# akabeacon_square_type2_MDBT40.net
KiCad netlist of a schematic drawn in EAGLE
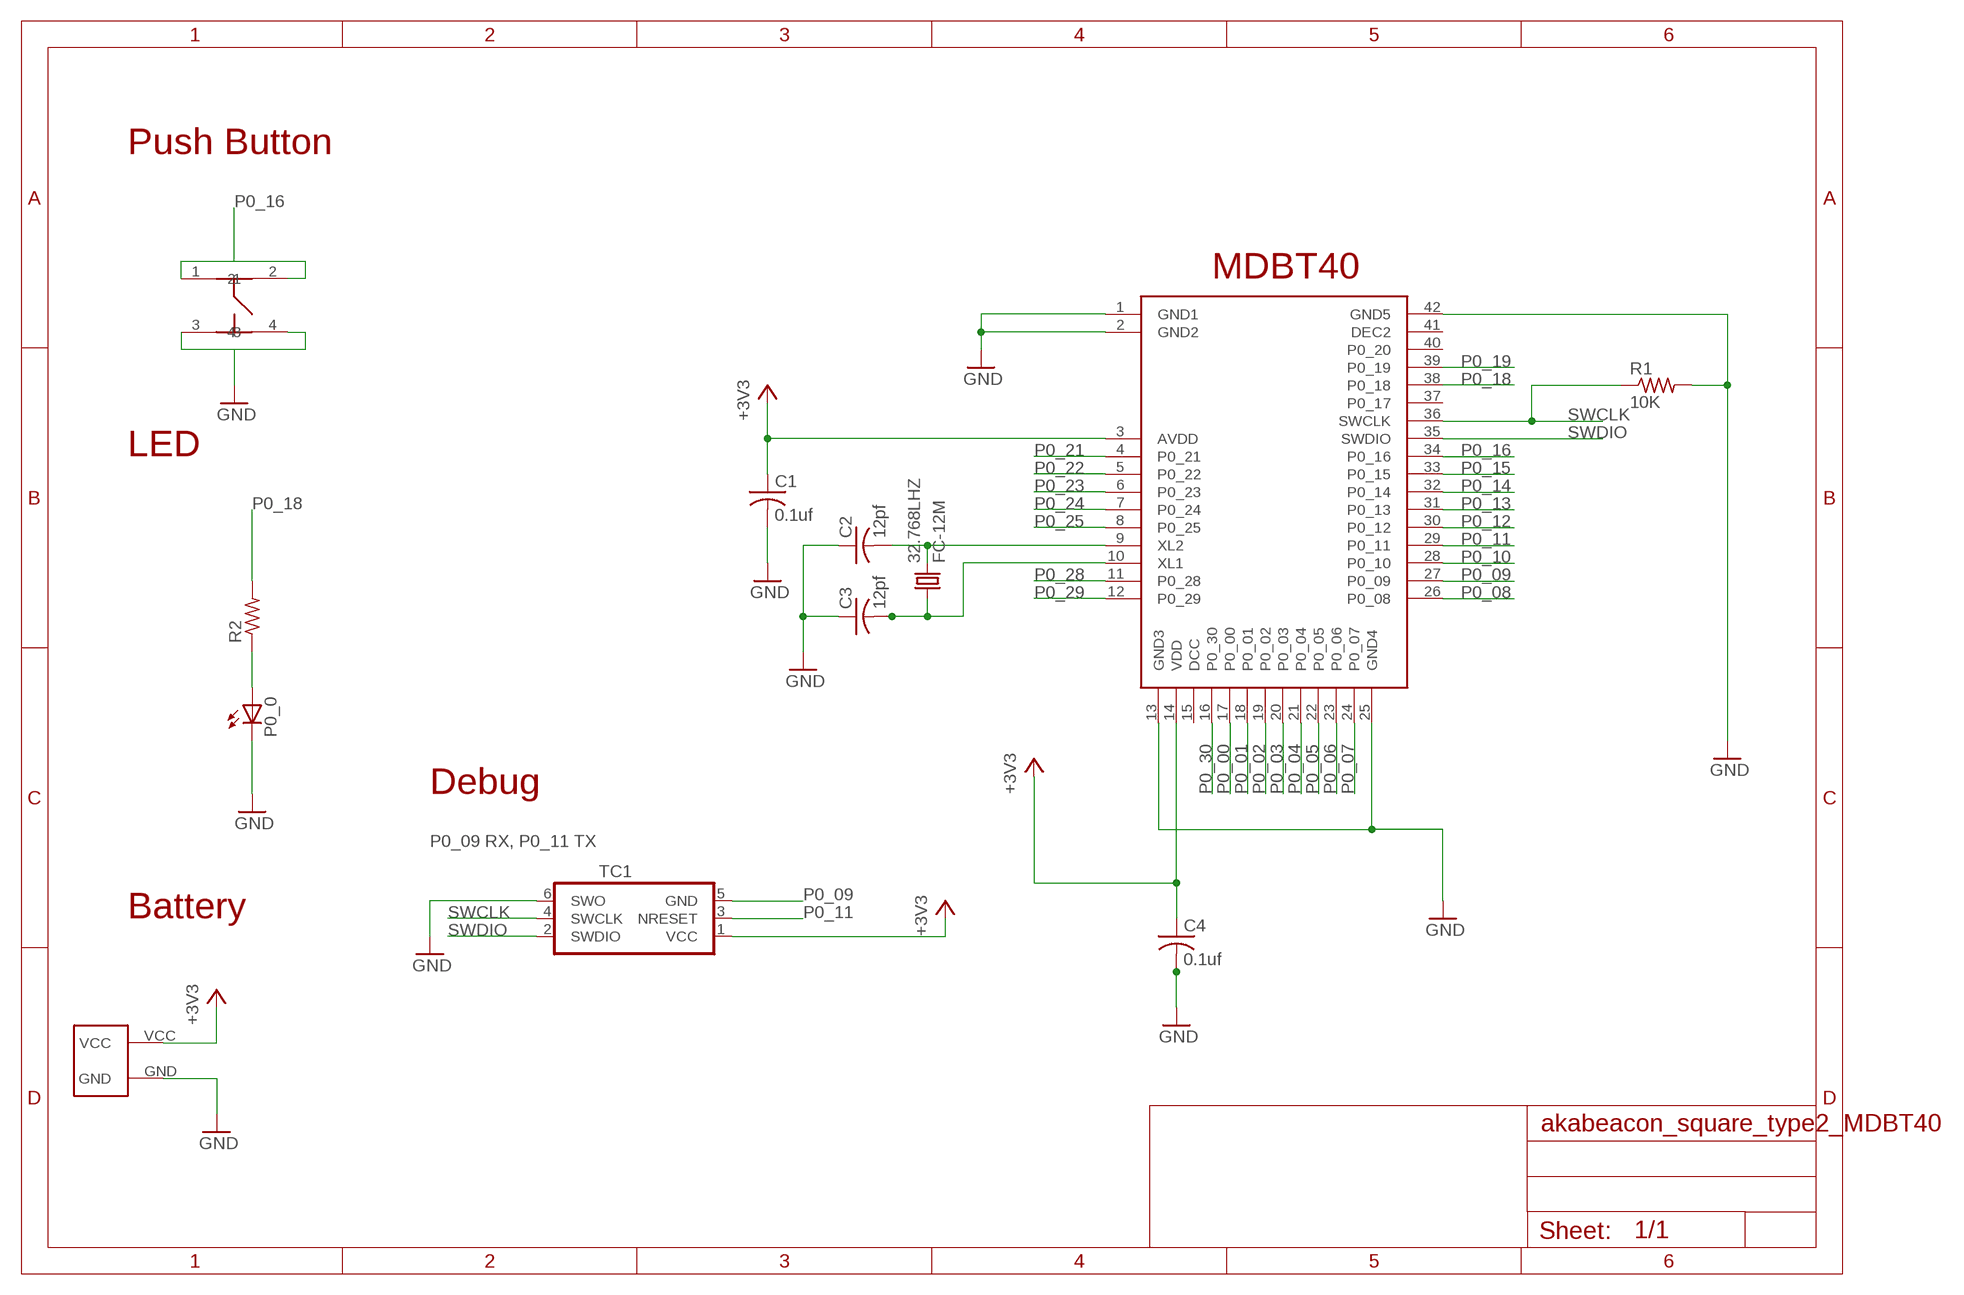
[diagram p0: schematic, sheet 1]

(export (version "E")
  (design (tool "Eeschema 10.0.6"))
  (components
    (comp (ref "32.768LHZ")
      (value "FC-12M")
      (footprint "eagle-import:FC-12M")
      (libsource (lib "eagle-import") (part "FC-12M"))
    )
    (comp (ref "C1")
      (value "0.1uf")
      (footprint "eagle-import:C0603")
      (libsource (lib "eagle-import") (part "C-USC0603"))
    )
    (comp (ref "C2")
      (value "12pf")
      (footprint "eagle-import:C0603")
      (libsource (lib "eagle-import") (part "C-USC0603"))
    )
    (comp (ref "C3")
      (value "12pf")
      (footprint "eagle-import:C0603")
      (libsource (lib "eagle-import") (part "C-USC0603"))
    )
    (comp (ref "C4")
      (value "0.1uf")
      (footprint "eagle-import:C0603")
      (libsource (lib "eagle-import") (part "C-USC0603"))
    )
    (comp (ref "P0_0")
      (value "LEDCHIP-LED0603")
      (footprint "eagle-import:CHIP-LED0603")
      (libsource (lib "eagle-import") (part "LEDCHIP-LED0603"))
    )
    (comp (ref "R1")
      (value "10K")
      (footprint "eagle-import:R0603")
      (libsource (lib "eagle-import") (part "R-US_R0603"))
    )
    (comp (ref "R2")
      (value "R-US_R0603")
      (footprint "eagle-import:R0603")
      (libsource (lib "eagle-import") (part "R-US_R0603"))
    )
    (comp (ref "TC1")
      (value "TC2030-IDC-NL")
      (footprint "eagle-import:TC2030-IDC-NL")
      (libsource (lib "eagle-import") (part "TC2030-IDC-NL"))
    )
    (comp (ref "U$3")
      (value "RAYTAC-MDBT40")
      (footprint "eagle-import:RAYTAC-MDBT40")
      (libsource (lib "eagle-import") (part "RAYTAC-MDBT40"))
    )
    (comp (ref "U$5")
      (value "SQUARE-TYPE2-TC2030")
      (footprint "eagle-import:SQUARE-TYPE2-TC2030")
      (libsource (lib "eagle-import") (part "SQUARE-TYPE2-TC2030"))
    )
    (comp (ref "U$6")
      (value "SWICTH-4P(KMR2)")
      (footprint "eagle-import:SWITCH-4P(KMR2)")
      (libsource (lib "eagle-import") (part "SWICTH-4P(KMR2)"))
    )
  )
  (nets
    (net (code "1") (name "+3V3") (class "Default")
      (node (ref "C1") (pin "1") (pinfunction "1_1") (pintype "passive"))
      (node (ref "C4") (pin "1") (pinfunction "1_1") (pintype "passive"))
      (node (ref "TC1") (pin "1") (pinfunction "VCC_1") (pintype "passive"))
      (node (ref "U$3") (pin "14") (pinfunction "VDD_14") (pintype "bidirectional"))
      (node (ref "U$3") (pin "3") (pinfunction "AVDD_3") (pintype "bidirectional"))
      (node (ref "U$5") (pin "VCC") (pinfunction "VCC_VCC") (pintype "bidirectional"))
    )
    (net (code "2") (name "/P0_00") (class "Default")
      (node (ref "U$3") (pin "17") (pinfunction "P0_00_17") (pintype "bidirectional"))
    )
    (net (code "3") (name "/P0_01") (class "Default")
      (node (ref "U$3") (pin "18") (pinfunction "P0_01_18") (pintype "bidirectional"))
    )
    (net (code "4") (name "/P0_02") (class "Default")
      (node (ref "U$3") (pin "19") (pinfunction "P0_02_19") (pintype "bidirectional"))
    )
    (net (code "5") (name "/P0_03") (class "Default")
      (node (ref "U$3") (pin "20") (pinfunction "P0_03_20") (pintype "bidirectional"))
    )
    (net (code "6") (name "/P0_04") (class "Default")
      (node (ref "U$3") (pin "21") (pinfunction "P0_04_21") (pintype "bidirectional"))
    )
    (net (code "7") (name "/P0_05") (class "Default")
      (node (ref "U$3") (pin "22") (pinfunction "P0_05_22") (pintype "bidirectional"))
    )
    (net (code "8") (name "/P0_06") (class "Default")
      (node (ref "U$3") (pin "23") (pinfunction "P0_06_23") (pintype "bidirectional"))
    )
    (net (code "9") (name "/P0_07") (class "Default")
      (node (ref "U$3") (pin "24") (pinfunction "P0_07_24") (pintype "bidirectional"))
    )
    (net (code "10") (name "/P0_08") (class "Default")
      (node (ref "U$3") (pin "26") (pinfunction "P0_08_26") (pintype "bidirectional"))
    )
    (net (code "11") (name "/P0_09") (class "Default")
      (node (ref "TC1") (pin "5") (pinfunction "GND_5") (pintype "passive"))
      (node (ref "U$3") (pin "27") (pinfunction "P0_09_27") (pintype "bidirectional"))
    )
    (net (code "12") (name "/P0_10") (class "Default")
      (node (ref "U$3") (pin "28") (pinfunction "P0_10_28") (pintype "bidirectional"))
    )
    (net (code "13") (name "/P0_11") (class "Default")
      (node (ref "TC1") (pin "3") (pinfunction "NRESET_3") (pintype "passive"))
      (node (ref "U$3") (pin "29") (pinfunction "P0_11_29") (pintype "bidirectional"))
    )
    (net (code "14") (name "/P0_12") (class "Default")
      (node (ref "U$3") (pin "30") (pinfunction "P0_12_30") (pintype "bidirectional"))
    )
    (net (code "15") (name "/P0_13") (class "Default")
      (node (ref "U$3") (pin "31") (pinfunction "P0_13_31") (pintype "bidirectional"))
    )
    (net (code "16") (name "/P0_14") (class "Default")
      (node (ref "U$3") (pin "32") (pinfunction "P0_14_32") (pintype "bidirectional"))
    )
    (net (code "17") (name "/P0_15") (class "Default")
      (node (ref "U$3") (pin "33") (pinfunction "P0_15_33") (pintype "bidirectional"))
    )
    (net (code "18") (name "/P0_16") (class "Default")
      (node (ref "U$3") (pin "34") (pinfunction "P0_16_34") (pintype "bidirectional"))
      (node (ref "U$6") (pin "1") (pinfunction "1_1") (pintype "bidirectional"))
      (node (ref "U$6") (pin "2") (pinfunction "2_2") (pintype "bidirectional"))
    )
    (net (code "19") (name "/P0_18") (class "Default")
      (node (ref "R2") (pin "2") (pinfunction "2_2") (pintype "passive"))
      (node (ref "U$3") (pin "38") (pinfunction "P0_18_38") (pintype "bidirectional"))
    )
    (net (code "20") (name "/P0_19") (class "Default")
      (node (ref "U$3") (pin "39") (pinfunction "P0_19_39") (pintype "bidirectional"))
    )
    (net (code "21") (name "/P0_21") (class "Default")
      (node (ref "U$3") (pin "4") (pinfunction "P0_21_4") (pintype "bidirectional"))
    )
    (net (code "22") (name "/P0_22") (class "Default")
      (node (ref "U$3") (pin "5") (pinfunction "P0_22_5") (pintype "bidirectional"))
    )
    (net (code "23") (name "/P0_23") (class "Default")
      (node (ref "U$3") (pin "6") (pinfunction "P0_23_6") (pintype "bidirectional"))
    )
    (net (code "24") (name "/P0_24") (class "Default")
      (node (ref "U$3") (pin "7") (pinfunction "P0_24_7") (pintype "bidirectional"))
    )
    (net (code "25") (name "/P0_25") (class "Default")
      (node (ref "U$3") (pin "8") (pinfunction "P0_25_8") (pintype "bidirectional"))
    )
    (net (code "26") (name "/P0_28") (class "Default")
      (node (ref "U$3") (pin "11") (pinfunction "P0_28_11") (pintype "bidirectional"))
    )
    (net (code "27") (name "/P0_29") (class "Default")
      (node (ref "U$3") (pin "12") (pinfunction "P0_29_12") (pintype "bidirectional"))
    )
    (net (code "28") (name "/P0_30") (class "Default")
      (node (ref "U$3") (pin "16") (pinfunction "P0_30_16") (pintype "bidirectional"))
    )
    (net (code "29") (name "/SWCLK") (class "Default")
      (node (ref "R1") (pin "1") (pinfunction "1_1") (pintype "passive"))
      (node (ref "TC1") (pin "4") (pinfunction "SWCLK_4") (pintype "passive"))
      (node (ref "U$3") (pin "36") (pinfunction "SWCLK_36") (pintype "bidirectional"))
    )
    (net (code "30") (name "/SWDIO") (class "Default")
      (node (ref "TC1") (pin "2") (pinfunction "SWDIO_2") (pintype "passive"))
      (node (ref "U$3") (pin "35") (pinfunction "SWDIO_35") (pintype "bidirectional"))
    )
    (net (code "31") (name "GND") (class "Default")
      (node (ref "C1") (pin "2") (pinfunction "2_2") (pintype "passive"))
      (node (ref "C2") (pin "1") (pinfunction "1_1") (pintype "passive"))
      (node (ref "C3") (pin "1") (pinfunction "1_1") (pintype "passive"))
      (node (ref "C4") (pin "2") (pinfunction "2_2") (pintype "passive"))
      (node (ref "P0_0") (pin "C") (pinfunction "C_C") (pintype "passive"))
      (node (ref "R1") (pin "2") (pinfunction "2_2") (pintype "passive"))
      (node (ref "TC1") (pin "6") (pinfunction "SWO_6") (pintype "passive"))
      (node (ref "U$3") (pin "1") (pinfunction "GND1_1") (pintype "bidirectional"))
      (node (ref "U$3") (pin "13") (pinfunction "GND3_13") (pintype "bidirectional"))
      (node (ref "U$3") (pin "2") (pinfunction "GND2_2") (pintype "bidirectional"))
      (node (ref "U$3") (pin "25") (pinfunction "GND4_25") (pintype "bidirectional"))
      (node (ref "U$3") (pin "42") (pinfunction "GND5_42") (pintype "bidirectional"))
      (node (ref "U$5") (pin "GND") (pinfunction "GND_GND") (pintype "bidirectional"))
      (node (ref "U$6") (pin "3") (pinfunction "3_3") (pintype "bidirectional"))
      (node (ref "U$6") (pin "4") (pinfunction "4_4") (pintype "bidirectional"))
    )
    (net (code "32") (name "Net-(P0_0-PadA)") (class "Default")
      (node (ref "P0_0") (pin "A") (pinfunction "A_A") (pintype "passive"))
      (node (ref "R2") (pin "1") (pinfunction "1_1") (pintype "passive"))
    )
    (net (code "33") (name "Net-(U$3-XL1)") (class "Default")
      (node (ref "32.768LHZ") (pin "1") (pinfunction "1_1") (pintype "passive"))
      (node (ref "C3") (pin "2") (pinfunction "2_2") (pintype "passive"))
      (node (ref "U$3") (pin "10") (pinfunction "XL1_10") (pintype "bidirectional"))
    )
    (net (code "34") (name "Net-(U$3-XL2)") (class "Default")
      (node (ref "32.768LHZ") (pin "2") (pinfunction "2_2") (pintype "passive"))
      (node (ref "C2") (pin "2") (pinfunction "2_2") (pintype "passive"))
      (node (ref "U$3") (pin "9") (pinfunction "XL2_9") (pintype "bidirectional"))
    )
    (net (code "35") (name "unconnected-(U$3-DCC-Pad15)") (class "Default")
      (node (ref "U$3") (pin "15") (pinfunction "DCC_15") (pintype "bidirectional"))
    )
    (net (code "36") (name "unconnected-(U$3-DEC2-Pad41)") (class "Default")
      (node (ref "U$3") (pin "41") (pinfunction "DEC2_41") (pintype "bidirectional"))
    )
    (net (code "37") (name "unconnected-(U$3-P0_17-Pad37)") (class "Default")
      (node (ref "U$3") (pin "37") (pinfunction "P0_17_37") (pintype "bidirectional"))
    )
    (net (code "38") (name "unconnected-(U$3-P0_20-Pad40)") (class "Default")
      (node (ref "U$3") (pin "40") (pinfunction "P0_20_40") (pintype "bidirectional"))
    )
  )
)
